# CANreader-HS.net
KiCad netlist of a schematic drawn in EAGLE
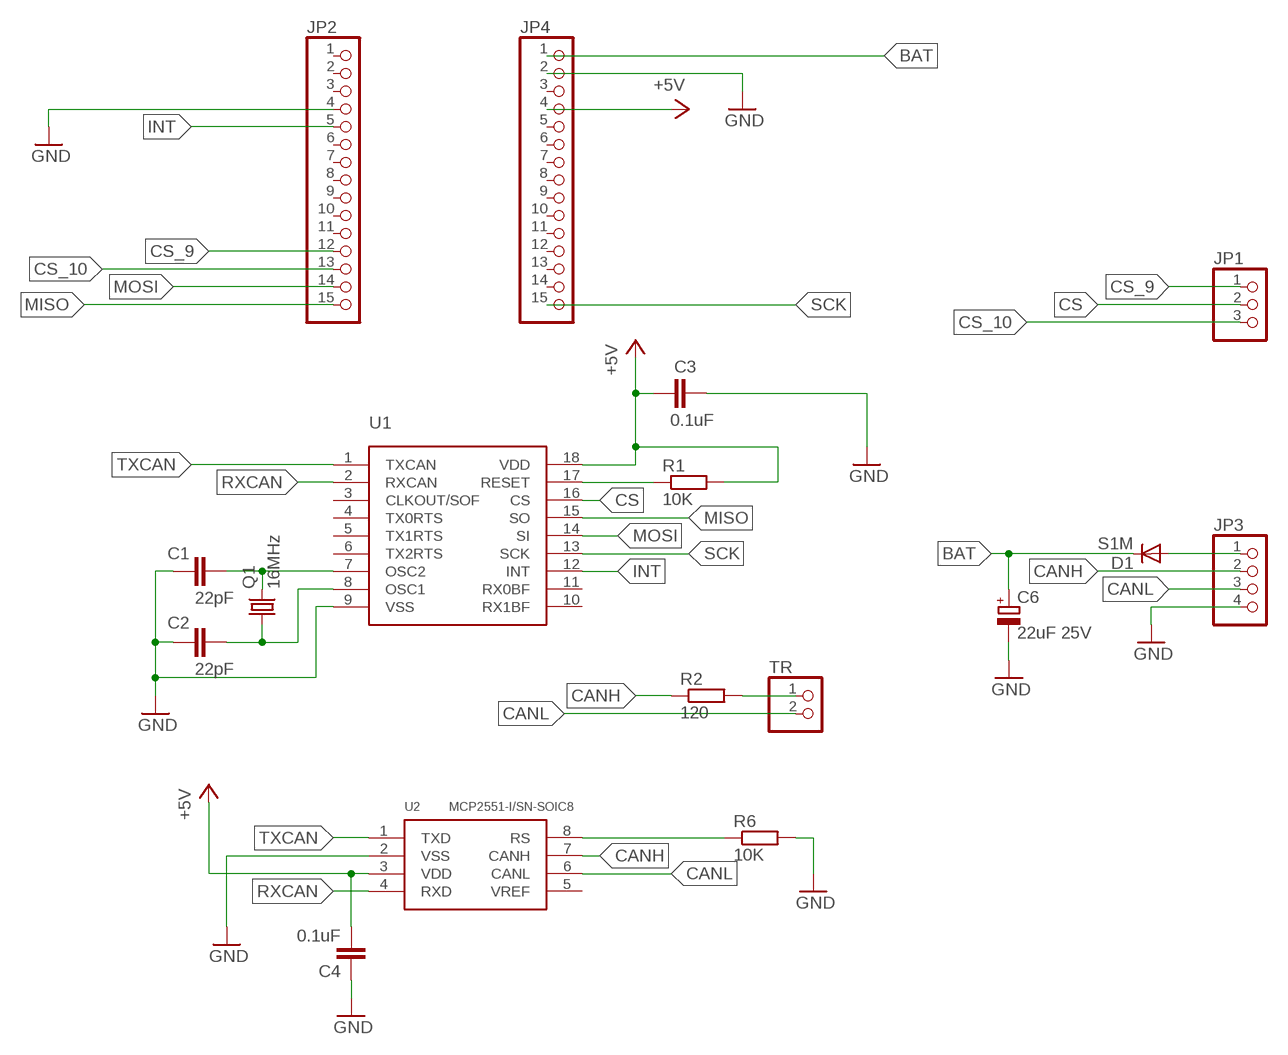
[diagram p0: schematic, sheet 1]

(export (version "E")
  (design (tool "Eeschema 10.0.6"))
  (components
    (comp (ref "C1")
      (value "22pF")
      (footprint "eagle-import:C0805")
      (libsource (lib "eagle-import") (part "C-EUC0805"))
    )
    (comp (ref "C2")
      (value "22pF")
      (footprint "eagle-import:C0805")
      (libsource (lib "eagle-import") (part "C-EUC0805"))
    )
    (comp (ref "C3")
      (value "0.1uF")
      (footprint "eagle-import:C0805")
      (libsource (lib "eagle-import") (part "C-EUC0805"))
    )
    (comp (ref "C4")
      (value "0.1uF")
      (footprint "eagle-import:C0805")
      (libsource (lib "eagle-import") (part "C-EUC0805"))
    )
    (comp (ref "C6")
      (value "22uF 25V")
      (footprint "eagle-import:SMC_C")
      (libsource (lib "eagle-import") (part "CPOL-EUSMCC"))
    )
    (comp (ref "D1")
      (value "S1M")
      (footprint "eagle-import:SMA")
      (libsource (lib "eagle-import") (part "S1M"))
    )
    (comp (ref "JP1")
      (value "PINHD-1X3")
      (footprint "eagle-import:1X03")
      (libsource (lib "eagle-import") (part "PINHD-1X3"))
    )
    (comp (ref "JP2")
      (value "PINHD-1X15")
      (footprint "eagle-import:1X15")
      (libsource (lib "eagle-import") (part "PINHD-1X15"))
    )
    (comp (ref "JP3")
      (value "PINHD-1X4-1")
      (footprint "eagle-import:1X04")
      (libsource (lib "eagle-import") (part "PINHD-1X4-1"))
    )
    (comp (ref "JP4")
      (value "PINHD-1X15")
      (footprint "eagle-import:1X15")
      (libsource (lib "eagle-import") (part "PINHD-1X15"))
    )
    (comp (ref "Q1")
      (value "16MHz")
      (footprint "eagle-import:HC49_S")
      (libsource (lib "eagle-import") (part "CRYSTALHC49S"))
    )
    (comp (ref "R1")
      (value "10K")
      (footprint "eagle-import:R0805")
      (libsource (lib "eagle-import") (part "R-EU_R0805"))
    )
    (comp (ref "R2")
      (value "120")
      (footprint "eagle-import:R0805")
      (libsource (lib "eagle-import") (part "R-EU_R0805"))
    )
    (comp (ref "R6")
      (value "10K")
      (footprint "eagle-import:R0805")
      (libsource (lib "eagle-import") (part "R-EU_R0805"))
    )
    (comp (ref "TR")
      (value "PINHD-1X2")
      (footprint "eagle-import:1X02")
      (libsource (lib "eagle-import") (part "PINHD-1X2"))
    )
    (comp (ref "U1")
      (value "MCP2515")
      (footprint "eagle-import:SO18-1")
      (libsource (lib "eagle-import") (part "MCP2515"))
    )
    (comp (ref "U2")
      (value "MCP2551-I/SN-SOIC8")
      (footprint "eagle-import:SOIC8-1.27-5X4MM")
      (fields (field (name "MPN") "MCP2551-I/SN"))
      (libsource (lib "eagle-import") (part "INTERFACE-MCP2551-I/SN(SOIC8)"))
    )
  )
  (nets
    (net (code "1") (name "+5V") (class "Default")
      (node (ref "C3") (pin "1") (pinfunction "1_1") (pintype "passive"))
      (node (ref "C4") (pin "2") (pinfunction "2_2") (pintype "passive"))
      (node (ref "JP4") (pin "4") (pinfunction "4_4") (pintype "passive"))
      (node (ref "R1") (pin "2") (pinfunction "2_2") (pintype "passive"))
      (node (ref "U1") (pin "18") (pinfunction "VDD_18") (pintype "power_in"))
      (node (ref "U2") (pin "3") (pinfunction "VDD_3") (pintype "bidirectional"))
    )
    (net (code "2") (name "BAT") (class "Default")
      (node (ref "C6") (pin "+") (pinfunction "+_+") (pintype "passive"))
      (node (ref "D1") (pin "C") (pinfunction "C_C") (pintype "passive"))
      (node (ref "JP4") (pin "1") (pinfunction "1_1") (pintype "passive"))
    )
    (net (code "3") (name "CANH") (class "Default")
      (node (ref "JP3") (pin "2") (pinfunction "2_2") (pintype "passive"))
      (node (ref "R2") (pin "1") (pinfunction "1_1") (pintype "passive"))
      (node (ref "U2") (pin "7") (pinfunction "CANH_7") (pintype "bidirectional"))
    )
    (net (code "4") (name "CANL") (class "Default")
      (node (ref "JP3") (pin "3") (pinfunction "3_3") (pintype "passive"))
      (node (ref "TR") (pin "2") (pinfunction "2_2") (pintype "passive"))
      (node (ref "U2") (pin "6") (pinfunction "CANL_6") (pintype "bidirectional"))
    )
    (net (code "5") (name "CS") (class "Default")
      (node (ref "JP1") (pin "2") (pinfunction "2_2") (pintype "passive"))
      (node (ref "U1") (pin "16") (pinfunction "CS_16") (pintype "bidirectional"))
    )
    (net (code "6") (name "CS_9") (class "Default")
      (node (ref "JP1") (pin "1") (pinfunction "1_1") (pintype "passive"))
      (node (ref "JP2") (pin "12") (pinfunction "12_12") (pintype "passive"))
    )
    (net (code "7") (name "CS_10") (class "Default")
      (node (ref "JP1") (pin "3") (pinfunction "3_3") (pintype "passive"))
      (node (ref "JP2") (pin "13") (pinfunction "13_13") (pintype "passive"))
    )
    (net (code "8") (name "GND") (class "Default")
      (node (ref "C1") (pin "1") (pinfunction "1_1") (pintype "passive"))
      (node (ref "C2") (pin "1") (pinfunction "1_1") (pintype "passive"))
      (node (ref "C3") (pin "2") (pinfunction "2_2") (pintype "passive"))
      (node (ref "C4") (pin "1") (pinfunction "1_1") (pintype "passive"))
      (node (ref "C6") (pin "-") (pinfunction "-_-") (pintype "passive"))
      (node (ref "JP2") (pin "4") (pinfunction "4_4") (pintype "passive"))
      (node (ref "JP3") (pin "4") (pinfunction "4_4") (pintype "passive"))
      (node (ref "JP4") (pin "2") (pinfunction "2_2") (pintype "passive"))
      (node (ref "R6") (pin "2") (pinfunction "2_2") (pintype "passive"))
      (node (ref "U1") (pin "9") (pinfunction "VSS_9") (pintype "power_in"))
      (node (ref "U2") (pin "2") (pinfunction "VSS_2") (pintype "bidirectional"))
    )
    (net (code "9") (name "INT") (class "Default")
      (node (ref "JP2") (pin "5") (pinfunction "5_5") (pintype "passive"))
      (node (ref "U1") (pin "12") (pinfunction "INT_12") (pintype "bidirectional"))
    )
    (net (code "10") (name "MISO") (class "Default")
      (node (ref "JP2") (pin "15") (pinfunction "15_15") (pintype "passive"))
      (node (ref "U1") (pin "15") (pinfunction "SO_15") (pintype "bidirectional"))
    )
    (net (code "11") (name "MOSI") (class "Default")
      (node (ref "JP2") (pin "14") (pinfunction "14_14") (pintype "passive"))
      (node (ref "U1") (pin "14") (pinfunction "SI_14") (pintype "bidirectional"))
    )
    (net (code "12") (name "Net-(D1-PadA)") (class "Default")
      (node (ref "D1") (pin "A") (pinfunction "A_A") (pintype "passive"))
      (node (ref "JP3") (pin "1") (pinfunction "1_1") (pintype "passive"))
    )
    (net (code "13") (name "Net-(R2-Pad2)") (class "Default")
      (node (ref "R2") (pin "2") (pinfunction "2_2") (pintype "passive"))
      (node (ref "TR") (pin "1") (pinfunction "1_1") (pintype "passive"))
    )
    (net (code "14") (name "Net-(U1-OSC1)") (class "Default")
      (node (ref "C2") (pin "2") (pinfunction "2_2") (pintype "passive"))
      (node (ref "Q1") (pin "1") (pinfunction "1_1") (pintype "passive"))
      (node (ref "U1") (pin "8") (pinfunction "OSC1_8") (pintype "bidirectional"))
    )
    (net (code "15") (name "Net-(U1-OSC2)") (class "Default")
      (node (ref "C1") (pin "2") (pinfunction "2_2") (pintype "passive"))
      (node (ref "Q1") (pin "2") (pinfunction "2_2") (pintype "passive"))
      (node (ref "U1") (pin "7") (pinfunction "OSC2_7") (pintype "bidirectional"))
    )
    (net (code "16") (name "Net-(U1-RESET)") (class "Default")
      (node (ref "R1") (pin "1") (pinfunction "1_1") (pintype "passive"))
      (node (ref "U1") (pin "17") (pinfunction "RESET_17") (pintype "bidirectional"))
    )
    (net (code "17") (name "Net-(U2-RS)") (class "Default")
      (node (ref "R6") (pin "1") (pinfunction "1_1") (pintype "passive"))
      (node (ref "U2") (pin "8") (pinfunction "RS_8") (pintype "bidirectional"))
    )
    (net (code "18") (name "RXCAN") (class "Default")
      (node (ref "U1") (pin "2") (pinfunction "RXCAN_2") (pintype "bidirectional"))
      (node (ref "U2") (pin "4") (pinfunction "RXD_4") (pintype "bidirectional"))
    )
    (net (code "19") (name "SCK") (class "Default")
      (node (ref "JP4") (pin "15") (pinfunction "15_15") (pintype "passive"))
      (node (ref "U1") (pin "13") (pinfunction "SCK_13") (pintype "bidirectional"))
    )
    (net (code "20") (name "TXCAN") (class "Default")
      (node (ref "U1") (pin "1") (pinfunction "TXCAN_1") (pintype "bidirectional"))
      (node (ref "U2") (pin "1") (pinfunction "TXD_1") (pintype "bidirectional"))
    )
    (net (code "21") (name "unconnected-(JP2-Pad1)") (class "Default")
      (node (ref "JP2") (pin "1") (pinfunction "1_1") (pintype "passive"))
    )
    (net (code "22") (name "unconnected-(JP2-Pad2)") (class "Default")
      (node (ref "JP2") (pin "2") (pinfunction "2_2") (pintype "passive"))
    )
    (net (code "23") (name "unconnected-(JP2-Pad3)") (class "Default")
      (node (ref "JP2") (pin "3") (pinfunction "3_3") (pintype "passive"))
    )
    (net (code "24") (name "unconnected-(JP2-Pad6)") (class "Default")
      (node (ref "JP2") (pin "6") (pinfunction "6_6") (pintype "passive"))
    )
    (net (code "25") (name "unconnected-(JP2-Pad7)") (class "Default")
      (node (ref "JP2") (pin "7") (pinfunction "7_7") (pintype "passive"))
    )
    (net (code "26") (name "unconnected-(JP2-Pad8)") (class "Default")
      (node (ref "JP2") (pin "8") (pinfunction "8_8") (pintype "passive"))
    )
    (net (code "27") (name "unconnected-(JP2-Pad9)") (class "Default")
      (node (ref "JP2") (pin "9") (pinfunction "9_9") (pintype "passive"))
    )
    (net (code "28") (name "unconnected-(JP2-Pad10)") (class "Default")
      (node (ref "JP2") (pin "10") (pinfunction "10_10") (pintype "passive"))
    )
    (net (code "29") (name "unconnected-(JP2-Pad11)") (class "Default")
      (node (ref "JP2") (pin "11") (pinfunction "11_11") (pintype "passive"))
    )
    (net (code "30") (name "unconnected-(JP4-Pad3)") (class "Default")
      (node (ref "JP4") (pin "3") (pinfunction "3_3") (pintype "passive"))
    )
    (net (code "31") (name "unconnected-(JP4-Pad5)") (class "Default")
      (node (ref "JP4") (pin "5") (pinfunction "5_5") (pintype "passive"))
    )
    (net (code "32") (name "unconnected-(JP4-Pad6)") (class "Default")
      (node (ref "JP4") (pin "6") (pinfunction "6_6") (pintype "passive"))
    )
    (net (code "33") (name "unconnected-(JP4-Pad7)") (class "Default")
      (node (ref "JP4") (pin "7") (pinfunction "7_7") (pintype "passive"))
    )
    (net (code "34") (name "unconnected-(JP4-Pad8)") (class "Default")
      (node (ref "JP4") (pin "8") (pinfunction "8_8") (pintype "passive"))
    )
    (net (code "35") (name "unconnected-(JP4-Pad9)") (class "Default")
      (node (ref "JP4") (pin "9") (pinfunction "9_9") (pintype "passive"))
    )
    (net (code "36") (name "unconnected-(JP4-Pad10)") (class "Default")
      (node (ref "JP4") (pin "10") (pinfunction "10_10") (pintype "passive"))
    )
    (net (code "37") (name "unconnected-(JP4-Pad11)") (class "Default")
      (node (ref "JP4") (pin "11") (pinfunction "11_11") (pintype "passive"))
    )
    (net (code "38") (name "unconnected-(JP4-Pad12)") (class "Default")
      (node (ref "JP4") (pin "12") (pinfunction "12_12") (pintype "passive"))
    )
    (net (code "39") (name "unconnected-(JP4-Pad13)") (class "Default")
      (node (ref "JP4") (pin "13") (pinfunction "13_13") (pintype "passive"))
    )
    (net (code "40") (name "unconnected-(JP4-Pad14)") (class "Default")
      (node (ref "JP4") (pin "14") (pinfunction "14_14") (pintype "passive"))
    )
    (net (code "41") (name "unconnected-(U1-CLKOUT{slash}SOF-Pad3)") (class "Default")
      (node (ref "U1") (pin "3") (pinfunction "CLKOUT/SOF_3") (pintype "bidirectional"))
    )
    (net (code "42") (name "unconnected-(U1-RX0BF-Pad11)") (class "Default")
      (node (ref "U1") (pin "11") (pinfunction "RX0BF_11") (pintype "bidirectional"))
    )
    (net (code "43") (name "unconnected-(U1-RX1BF-Pad10)") (class "Default")
      (node (ref "U1") (pin "10") (pinfunction "RX1BF_10") (pintype "bidirectional"))
    )
    (net (code "44") (name "unconnected-(U1-TX0RTS-Pad4)") (class "Default")
      (node (ref "U1") (pin "4") (pinfunction "TX0RTS_4") (pintype "bidirectional"))
    )
    (net (code "45") (name "unconnected-(U1-TX1RTS-Pad5)") (class "Default")
      (node (ref "U1") (pin "5") (pinfunction "TX1RTS_5") (pintype "bidirectional"))
    )
    (net (code "46") (name "unconnected-(U1-TX2RTS-Pad6)") (class "Default")
      (node (ref "U1") (pin "6") (pinfunction "TX2RTS_6") (pintype "bidirectional"))
    )
    (net (code "47") (name "unconnected-(U2-VREF-Pad5)") (class "Default")
      (node (ref "U2") (pin "5") (pinfunction "VREF_5") (pintype "bidirectional"))
    )
  )
)
